# CCU_board.net
KiCad netlist of a schematic drawn in EAGLE
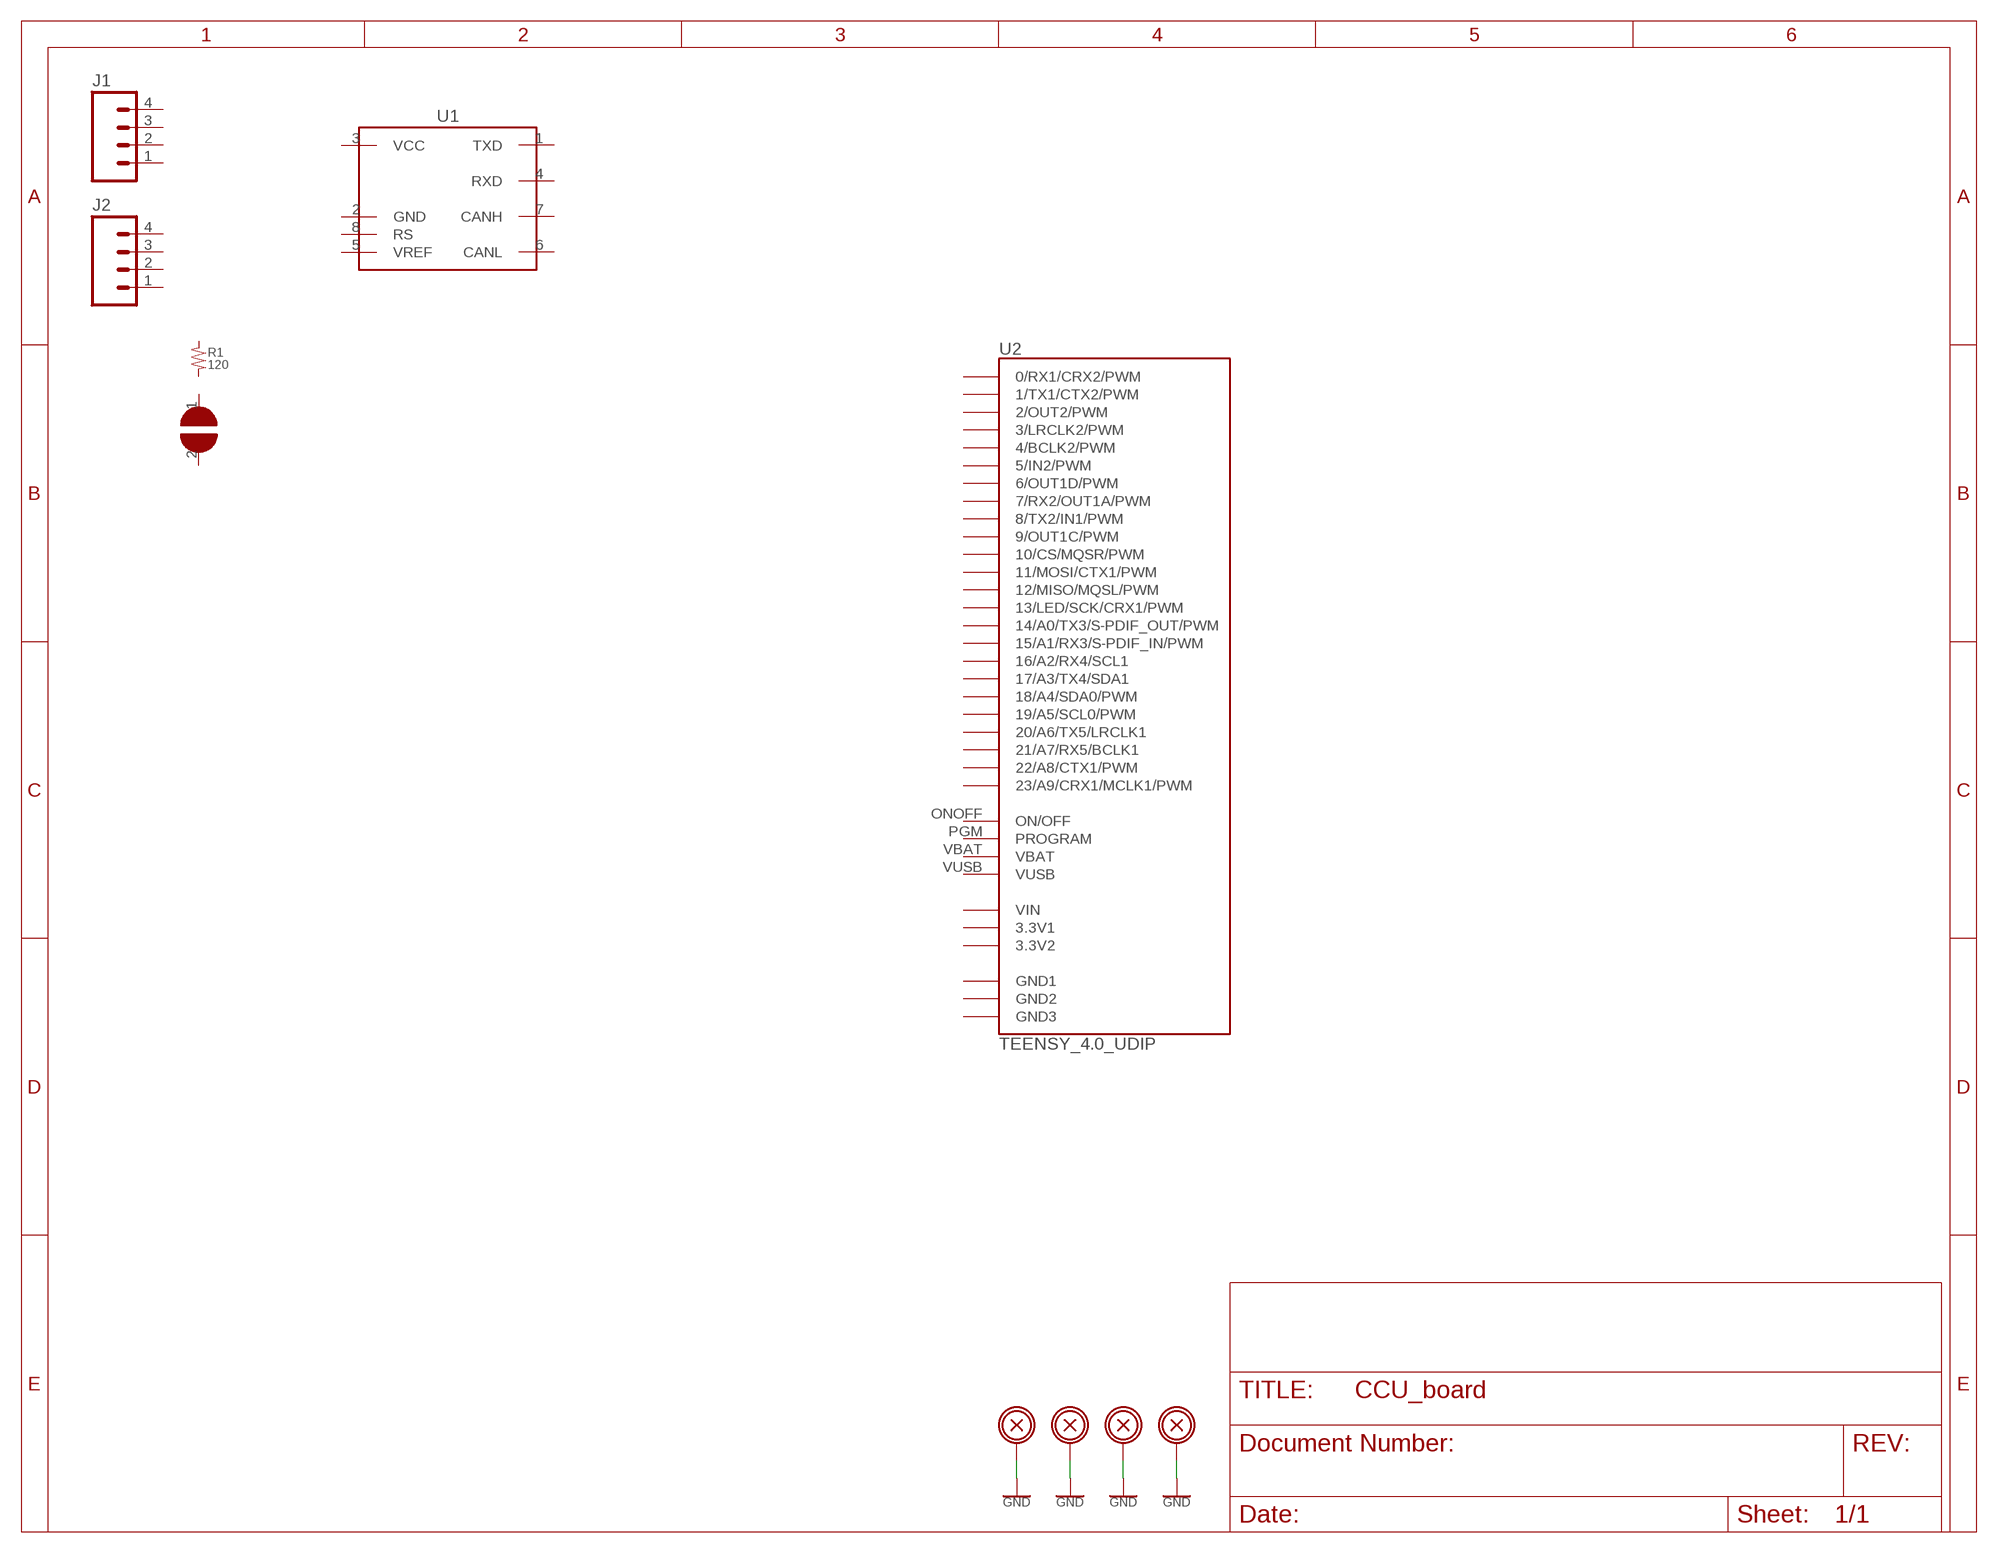
[diagram p0: schematic, sheet 1]

(export (version "E")
  (design (tool "Eeschema 10.0.6"))
  (components
    (comp (ref "H1")
      (value "BOLTHOLE_M3")
      (footprint "eagle-import:M3_HOLE")
      (libsource (lib "eagle-import") (part "BOLTHOLE_M3"))
    )
    (comp (ref "H2")
      (value "BOLTHOLE_M3")
      (footprint "eagle-import:M3_HOLE")
      (libsource (lib "eagle-import") (part "BOLTHOLE_M3"))
    )
    (comp (ref "H3")
      (value "BOLTHOLE_M3")
      (footprint "eagle-import:M3_HOLE")
      (libsource (lib "eagle-import") (part "BOLTHOLE_M3"))
    )
    (comp (ref "H4")
      (value "BOLTHOLE_M3")
      (footprint "eagle-import:M3_HOLE")
      (libsource (lib "eagle-import") (part "BOLTHOLE_M3"))
    )
    (comp (ref "J1")
      (value "SM04B-SRSS-TB")
      (footprint "eagle-import:SM04B-SRSS-TB")
      (libsource (lib "eagle-import") (part "?M04B-SRSS-TBS"))
    )
    (comp (ref "J2")
      (value "SM04B-SRSS-TB")
      (footprint "eagle-import:SM04B-SRSS-TB")
      (libsource (lib "eagle-import") (part "?M04B-SRSS-TBS"))
    )
    (comp (ref "R1")
      (value "120")
      (footprint "eagle-import:0402")
      (libsource (lib "eagle-import") (part "RES_SMD_0402"))
    )
    (comp (ref "SJ1")
      (value "SOLDERABLE_JUMPER_1POS_NP")
      (footprint "eagle-import:SJ_2S-NO")
      (libsource (lib "eagle-import") (part "SOLDERABLE_JUMPER_1POS_NP"))
    )
    (comp (ref "U1")
      (value "SN65HVD23X")
      (footprint "eagle-import:SOIC_8")
      (libsource (lib "eagle-import") (part "SN65HVD23X"))
    )
    (comp (ref "U2")
      (value "TEENSY_4.0_UDIP")
      (footprint "eagle-import:TEENSY_4.0_UDIP")
      (libsource (lib "eagle-import") (part "TEENSY_4.0_UDIP"))
    )
  )
  (nets
    (net (code "1") (name "/3.3V1") (class "Default")
      (node (ref "U2") (pin "3.3V1") (pinfunction "3.3V1_3.3V1") (pintype "power_in"))
    )
    (net (code "2") (name "/3.3V2") (class "Default")
      (node (ref "U2") (pin "3.3V2") (pinfunction "3.3V2_3.3V2") (pintype "power_in"))
    )
    (net (code "3") (name "/GND1") (class "Default")
      (node (ref "U2") (pin "GND1") (pinfunction "GND1_GND1") (pintype "power_in"))
    )
    (net (code "4") (name "/GND2") (class "Default")
      (node (ref "U2") (pin "GND2") (pinfunction "GND2_GND2") (pintype "power_in"))
    )
    (net (code "5") (name "/GND3") (class "Default")
      (node (ref "U2") (pin "GND3") (pinfunction "GND3_GND3") (pintype "power_in"))
    )
    (net (code "6") (name "/VIN") (class "Default")
      (node (ref "U2") (pin "VIN") (pinfunction "VIN_VIN") (pintype "power_in"))
    )
    (net (code "7") (name "GND") (class "Default")
      (node (ref "H1") (pin "P") (pinfunction "P_P") (pintype "bidirectional"))
      (node (ref "H2") (pin "P") (pinfunction "P_P") (pintype "bidirectional"))
      (node (ref "H3") (pin "P") (pinfunction "P_P") (pintype "bidirectional"))
      (node (ref "H4") (pin "P") (pinfunction "P_P") (pintype "bidirectional"))
    )
    (net (code "8") (name "unconnected-(J1-Pad1)") (class "Default")
      (node (ref "J1") (pin "1") (pinfunction "1_1") (pintype "passive"))
    )
    (net (code "9") (name "unconnected-(J1-Pad2)") (class "Default")
      (node (ref "J1") (pin "2") (pinfunction "2_2") (pintype "passive"))
    )
    (net (code "10") (name "unconnected-(J1-Pad3)") (class "Default")
      (node (ref "J1") (pin "3") (pinfunction "3_3") (pintype "passive"))
    )
    (net (code "11") (name "unconnected-(J1-Pad4)") (class "Default")
      (node (ref "J1") (pin "4") (pinfunction "4_4") (pintype "passive"))
    )
    (net (code "12") (name "unconnected-(J2-Pad1)") (class "Default")
      (node (ref "J2") (pin "1") (pinfunction "1_1") (pintype "passive"))
    )
    (net (code "13") (name "unconnected-(J2-Pad2)") (class "Default")
      (node (ref "J2") (pin "2") (pinfunction "2_2") (pintype "passive"))
    )
    (net (code "14") (name "unconnected-(J2-Pad3)") (class "Default")
      (node (ref "J2") (pin "3") (pinfunction "3_3") (pintype "passive"))
    )
    (net (code "15") (name "unconnected-(J2-Pad4)") (class "Default")
      (node (ref "J2") (pin "4") (pinfunction "4_4") (pintype "passive"))
    )
    (net (code "16") (name "unconnected-(R1-Pad1)") (class "Default")
      (node (ref "R1") (pin "1") (pinfunction "1_1") (pintype "passive"))
    )
    (net (code "17") (name "unconnected-(R1-Pad2)") (class "Default")
      (node (ref "R1") (pin "2") (pinfunction "2_2") (pintype "passive"))
    )
    (net (code "18") (name "unconnected-(SJ1-Pad1)") (class "Default")
      (node (ref "SJ1") (pin "1") (pinfunction "1_1") (pintype "bidirectional"))
    )
    (net (code "19") (name "unconnected-(SJ1-Pad2)") (class "Default")
      (node (ref "SJ1") (pin "2") (pinfunction "2_2") (pintype "bidirectional"))
    )
    (net (code "20") (name "unconnected-(U1-CANH-Pad7)") (class "Default")
      (node (ref "U1") (pin "7") (pinfunction "CANH_7") (pintype "bidirectional"))
    )
    (net (code "21") (name "unconnected-(U1-CANL-Pad6)") (class "Default")
      (node (ref "U1") (pin "6") (pinfunction "CANL_6") (pintype "bidirectional"))
    )
    (net (code "22") (name "unconnected-(U1-GND-Pad2)") (class "Default")
      (node (ref "U1") (pin "2") (pinfunction "GND_2") (pintype "bidirectional"))
    )
    (net (code "23") (name "unconnected-(U1-RS-Pad8)") (class "Default")
      (node (ref "U1") (pin "8") (pinfunction "RS_8") (pintype "bidirectional"))
    )
    (net (code "24") (name "unconnected-(U1-RXD-Pad4)") (class "Default")
      (node (ref "U1") (pin "4") (pinfunction "RXD_4") (pintype "bidirectional"))
    )
    (net (code "25") (name "unconnected-(U1-TXD-Pad1)") (class "Default")
      (node (ref "U1") (pin "1") (pinfunction "TXD_1") (pintype "bidirectional"))
    )
    (net (code "26") (name "unconnected-(U1-VCC-Pad3)") (class "Default")
      (node (ref "U1") (pin "3") (pinfunction "VCC_3") (pintype "bidirectional"))
    )
    (net (code "27") (name "unconnected-(U1-VREF-Pad5)") (class "Default")
      (node (ref "U1") (pin "5") (pinfunction "VREF_5") (pintype "bidirectional"))
    )
    (net (code "28") (name "unconnected-(U2-0{slash}RX1{slash}CRX2{slash}PWM-Pad0)") (class "Default")
      (node (ref "U2") (pin "0") (pinfunction "0/RX1/CRX2/PWM_0") (pintype "bidirectional"))
    )
    (net (code "29") (name "unconnected-(U2-1{slash}TX1{slash}CTX2{slash}PWM-Pad1)") (class "Default")
      (node (ref "U2") (pin "1") (pinfunction "1/TX1/CTX2/PWM_1") (pintype "bidirectional"))
    )
    (net (code "30") (name "unconnected-(U2-2{slash}OUT2{slash}PWM-Pad2)") (class "Default")
      (node (ref "U2") (pin "2") (pinfunction "2/OUT2/PWM_2") (pintype "bidirectional"))
    )
    (net (code "31") (name "unconnected-(U2-3{slash}LRCLK2{slash}PWM-Pad3)") (class "Default")
      (node (ref "U2") (pin "3") (pinfunction "3/LRCLK2/PWM_3") (pintype "bidirectional"))
    )
    (net (code "32") (name "unconnected-(U2-4{slash}BCLK2{slash}PWM-Pad4)") (class "Default")
      (node (ref "U2") (pin "4") (pinfunction "4/BCLK2/PWM_4") (pintype "bidirectional"))
    )
    (net (code "33") (name "unconnected-(U2-5{slash}IN2{slash}PWM-Pad5)") (class "Default")
      (node (ref "U2") (pin "5") (pinfunction "5/IN2/PWM_5") (pintype "bidirectional"))
    )
    (net (code "34") (name "unconnected-(U2-6{slash}OUT1D{slash}PWM-Pad6)") (class "Default")
      (node (ref "U2") (pin "6") (pinfunction "6/OUT1D/PWM_6") (pintype "bidirectional"))
    )
    (net (code "35") (name "unconnected-(U2-7{slash}RX2{slash}OUT1A{slash}PWM-Pad7)") (class "Default")
      (node (ref "U2") (pin "7") (pinfunction "7/RX2/OUT1A/PWM_7") (pintype "bidirectional"))
    )
    (net (code "36") (name "unconnected-(U2-8{slash}TX2{slash}IN1{slash}PWM-Pad8)") (class "Default")
      (node (ref "U2") (pin "8") (pinfunction "8/TX2/IN1/PWM_8") (pintype "bidirectional"))
    )
    (net (code "37") (name "unconnected-(U2-9{slash}OUT1C{slash}PWM-Pad9)") (class "Default")
      (node (ref "U2") (pin "9") (pinfunction "9/OUT1C/PWM_9") (pintype "bidirectional"))
    )
    (net (code "38") (name "unconnected-(U2-10{slash}CS{slash}MQSR{slash}PWM-Pad10)") (class "Default")
      (node (ref "U2") (pin "10") (pinfunction "10/CS/MQSR/PWM_10") (pintype "bidirectional"))
    )
    (net (code "39") (name "unconnected-(U2-11{slash}MOSI{slash}CTX1{slash}PWM-Pad11)") (class "Default")
      (node (ref "U2") (pin "11") (pinfunction "11/MOSI/CTX1/PWM_11") (pintype "bidirectional"))
    )
    (net (code "40") (name "unconnected-(U2-12{slash}MISO{slash}MQSL{slash}PWM-Pad12)") (class "Default")
      (node (ref "U2") (pin "12") (pinfunction "12/MISO/MQSL/PWM_12") (pintype "bidirectional"))
    )
    (net (code "41") (name "unconnected-(U2-13{slash}LED{slash}SCK{slash}CRX1{slash}PWM-Pad13)") (class "Default")
      (node (ref "U2") (pin "13") (pinfunction "13/LED/SCK/CRX1/PWM_13") (pintype "bidirectional"))
    )
    (net (code "42") (name "unconnected-(U2-14{slash}A0{slash}TX3{slash}S-PDIF_OUT{slash}PWM-Pad14)") (class "Default")
      (node (ref "U2") (pin "14") (pinfunction "14/A0/TX3/S-PDIF_OUT/PWM_14") (pintype "bidirectional"))
    )
    (net (code "43") (name "unconnected-(U2-15{slash}A1{slash}RX3{slash}S-PDIF_IN{slash}PWM-Pad15)") (class "Default")
      (node (ref "U2") (pin "15") (pinfunction "15/A1/RX3/S-PDIF_IN/PWM_15") (pintype "bidirectional"))
    )
    (net (code "44") (name "unconnected-(U2-16{slash}A2{slash}RX4{slash}SCL1-Pad16)") (class "Default")
      (node (ref "U2") (pin "16") (pinfunction "16/A2/RX4/SCL1_16") (pintype "bidirectional"))
    )
    (net (code "45") (name "unconnected-(U2-17{slash}A3{slash}TX4{slash}SDA1-Pad17)") (class "Default")
      (node (ref "U2") (pin "17") (pinfunction "17/A3/TX4/SDA1_17") (pintype "bidirectional"))
    )
    (net (code "46") (name "unconnected-(U2-18{slash}A4{slash}SDA0{slash}PWM-Pad18)") (class "Default")
      (node (ref "U2") (pin "18") (pinfunction "18/A4/SDA0/PWM_18") (pintype "bidirectional"))
    )
    (net (code "47") (name "unconnected-(U2-19{slash}A5{slash}SCL0{slash}PWM-Pad19)") (class "Default")
      (node (ref "U2") (pin "19") (pinfunction "19/A5/SCL0/PWM_19") (pintype "bidirectional"))
    )
    (net (code "48") (name "unconnected-(U2-20{slash}A6{slash}TX5{slash}LRCLK1-Pad20)") (class "Default")
      (node (ref "U2") (pin "20") (pinfunction "20/A6/TX5/LRCLK1_20") (pintype "bidirectional"))
    )
    (net (code "49") (name "unconnected-(U2-21{slash}A7{slash}RX5{slash}BCLK1-Pad21)") (class "Default")
      (node (ref "U2") (pin "21") (pinfunction "21/A7/RX5/BCLK1_21") (pintype "bidirectional"))
    )
    (net (code "50") (name "unconnected-(U2-22{slash}A8{slash}CTX1{slash}PWM-Pad22)") (class "Default")
      (node (ref "U2") (pin "22") (pinfunction "22/A8/CTX1/PWM_22") (pintype "bidirectional"))
    )
    (net (code "51") (name "unconnected-(U2-23{slash}A9{slash}CRX1{slash}MCLK1{slash}PWM-Pad23)") (class "Default")
      (node (ref "U2") (pin "23") (pinfunction "23/A9/CRX1/MCLK1/PWM_23") (pintype "bidirectional"))
    )
    (net (code "52") (name "unconnected-(U2-ON{slash}OFF-PadONOFF)") (class "Default")
      (node (ref "U2") (pin "ONOFF") (pinfunction "ON/OFF_ONOFF") (pintype "bidirectional"))
    )
    (net (code "53") (name "unconnected-(U2-PROGRAM-PadPGM)") (class "Default")
      (node (ref "U2") (pin "PGM") (pinfunction "PROGRAM_PGM") (pintype "bidirectional"))
    )
    (net (code "54") (name "unconnected-(U2-PadVBAT)") (class "Default")
      (node (ref "U2") (pin "VBAT") (pinfunction "VBAT_VBAT") (pintype "bidirectional"))
    )
    (net (code "55") (name "unconnected-(U2-PadVUSB)") (class "Default")
      (node (ref "U2") (pin "VUSB") (pinfunction "VUSB_VUSB") (pintype "bidirectional"))
    )
  )
)
